# ESP-01_Tamer-u.net
KiCad netlist of a schematic drawn in EAGLE
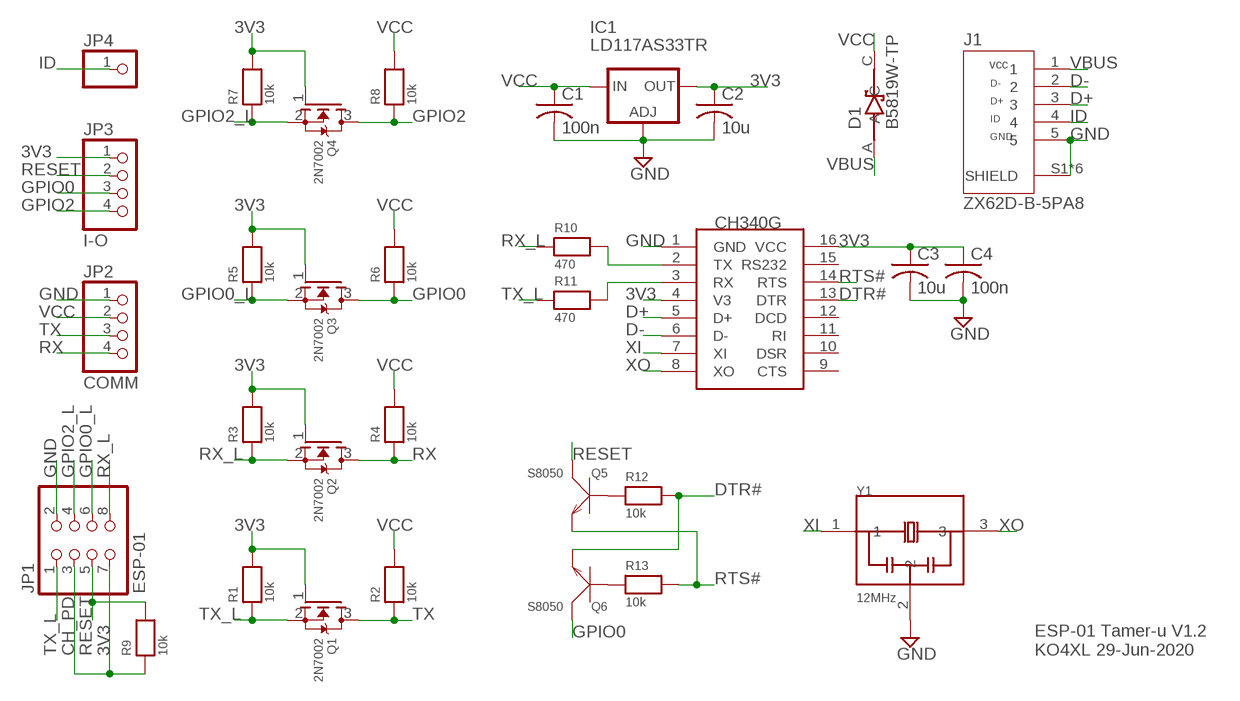
[diagram p0: schematic, sheet 1]

(export (version "E")
  (design (tool "Eeschema 10.0.6"))
  (components
    (comp (ref "C1")
      (value "100n")
      (footprint "eagle-import:C0805K")
      (libsource (lib "eagle-import") (part "C-USC0805K"))
    )
    (comp (ref "C2")
      (value "10u")
      (footprint "eagle-import:C0805K")
      (libsource (lib "eagle-import") (part "C-USC0805K"))
    )
    (comp (ref "C3")
      (value "10u")
      (footprint "eagle-import:C0805K")
      (libsource (lib "eagle-import") (part "C-USC0805K"))
    )
    (comp (ref "C4")
      (value "100n")
      (footprint "eagle-import:C0805K")
      (libsource (lib "eagle-import") (part "C-USC0805K"))
    )
    (comp (ref "D1")
      (value "B5819W-TP")
      (footprint "eagle-import:SOD3716X135N")
      (fields (field (name "MF") "Micro Commercial"))
      (libsource (lib "eagle-import") (part "B5819W-TP"))
    )
    (comp (ref "IC1")
      (value "LD117AS33TR")
      (footprint "eagle-import:SOT223")
      (libsource (lib "eagle-import") (part "LD117A?S33TR"))
    )
    (comp (ref "IC2")
      (value "CH340G")
      (footprint "eagle-import:SOIC16")
      (libsource (lib "eagle-import") (part "CH340G"))
    )
    (comp (ref "J1")
      (value "ZX62D-B-5PA8")
      (footprint "eagle-import:HIROSE_ZX62D-B-5PA8")
      (fields (field (name "MF") "Hirose"))
      (libsource (lib "eagle-import") (part "ZX62D-B-5PA8"))
    )
    (comp (ref "JP1")
      (value "ESP-01")
      (footprint "eagle-import:2X04")
      (libsource (lib "eagle-import") (part "PINHD-2X4"))
    )
    (comp (ref "JP2")
      (value "COMM")
      (footprint "eagle-import:1X04_ROUND")
      (libsource (lib "eagle-import") (part "HEADER-1X4ROUND"))
    )
    (comp (ref "JP3")
      (value "I-O")
      (footprint "eagle-import:1X04_ROUND")
      (libsource (lib "eagle-import") (part "HEADER-1X4ROUND"))
    )
    (comp (ref "JP4")
      (value "HEADER-1X1ROUND")
      (footprint "eagle-import:1X01_ROUND")
      (libsource (lib "eagle-import") (part "HEADER-1X1ROUND"))
    )
    (comp (ref "Q1")
      (value "2N7002")
      (footprint "eagle-import:SOT23-WIDE")
      (libsource (lib "eagle-import") (part "MOSFET-NWIDE"))
    )
    (comp (ref "Q2")
      (value "2N7002")
      (footprint "eagle-import:SOT23-WIDE")
      (libsource (lib "eagle-import") (part "MOSFET-NWIDE"))
    )
    (comp (ref "Q3")
      (value "2N7002")
      (footprint "eagle-import:SOT23-WIDE")
      (libsource (lib "eagle-import") (part "MOSFET-NWIDE"))
    )
    (comp (ref "Q4")
      (value "2N7002")
      (footprint "eagle-import:SOT23-WIDE")
      (libsource (lib "eagle-import") (part "MOSFET-NWIDE"))
    )
    (comp (ref "Q5")
      (value "S8050")
      (footprint "eagle-import:SOT-23")
      (fields (field (name "MF") "JCET"))
      (libsource (lib "eagle-import") (part "SMD-TRANSISTORS-NPN-25V-500MW-S8050(SOT-23)"))
    )
    (comp (ref "Q6")
      (value "S8050")
      (footprint "eagle-import:SOT-23")
      (fields (field (name "MF") "JCET"))
      (libsource (lib "eagle-import") (part "SMD-TRANSISTORS-NPN-25V-500MW-S8050(SOT-23)"))
    )
    (comp (ref "R1")
      (value "10k")
      (footprint "eagle-import:0805_NOTHERMALS")
      (libsource (lib "eagle-import") (part "RESISTOR0805_NOTHERMALS"))
    )
    (comp (ref "R2")
      (value "10k")
      (footprint "eagle-import:0805_NOTHERMALS")
      (libsource (lib "eagle-import") (part "RESISTOR0805_NOTHERMALS"))
    )
    (comp (ref "R3")
      (value "10k")
      (footprint "eagle-import:0805_NOTHERMALS")
      (libsource (lib "eagle-import") (part "RESISTOR0805_NOTHERMALS"))
    )
    (comp (ref "R4")
      (value "10k")
      (footprint "eagle-import:0805_NOTHERMALS")
      (libsource (lib "eagle-import") (part "RESISTOR0805_NOTHERMALS"))
    )
    (comp (ref "R5")
      (value "10k")
      (footprint "eagle-import:0805_NOTHERMALS")
      (libsource (lib "eagle-import") (part "RESISTOR0805_NOTHERMALS"))
    )
    (comp (ref "R6")
      (value "10k")
      (footprint "eagle-import:0805_NOTHERMALS")
      (libsource (lib "eagle-import") (part "RESISTOR0805_NOTHERMALS"))
    )
    (comp (ref "R7")
      (value "10k")
      (footprint "eagle-import:0805_NOTHERMALS")
      (libsource (lib "eagle-import") (part "RESISTOR0805_NOTHERMALS"))
    )
    (comp (ref "R8")
      (value "10k")
      (footprint "eagle-import:0805_NOTHERMALS")
      (libsource (lib "eagle-import") (part "RESISTOR0805_NOTHERMALS"))
    )
    (comp (ref "R9")
      (value "10k")
      (footprint "eagle-import:0805_NOTHERMALS")
      (libsource (lib "eagle-import") (part "RESISTOR0805_NOTHERMALS"))
    )
    (comp (ref "R10")
      (value "470")
      (footprint "eagle-import:0805_NOTHERMALS")
      (libsource (lib "eagle-import") (part "RESISTOR0805_NOTHERMALS"))
    )
    (comp (ref "R11")
      (value "470")
      (footprint "eagle-import:0805_NOTHERMALS")
      (libsource (lib "eagle-import") (part "RESISTOR0805_NOTHERMALS"))
    )
    (comp (ref "R12")
      (value "10k")
      (footprint "eagle-import:0805_NOTHERMALS")
      (libsource (lib "eagle-import") (part "RESISTOR0805_NOTHERMALS"))
    )
    (comp (ref "R13")
      (value "10k")
      (footprint "eagle-import:0805_NOTHERMALS")
      (libsource (lib "eagle-import") (part "RESISTOR0805_NOTHERMALS"))
    )
    (comp (ref "Y1")
      (value "12MHz")
      (footprint "eagle-import:OSC_CSTCE8M00G55-R0")
      (fields (field (name "MF") "Murata") (field (name "MP") "CSTCE8M00G55-R0"))
      (libsource (lib "eagle-import") (part "CSTCE8M00G55-R0"))
    )
  )
  (nets
    (net (code "1") (name "/3V3") (class "Default")
      (node (ref "C2") (pin "1") (pinfunction "1_1") (pintype "passive"))
      (node (ref "C3") (pin "1") (pinfunction "1_1") (pintype "passive"))
      (node (ref "C4") (pin "1") (pinfunction "1_1") (pintype "passive"))
      (node (ref "IC1") (pin "4") (pinfunction "OUT_4") (pintype "passive"))
      (node (ref "IC2") (pin "16") (pinfunction "VCC_16") (pintype "bidirectional"))
      (node (ref "IC2") (pin "4") (pinfunction "V3_4") (pintype "bidirectional"))
      (node (ref "JP1") (pin "3") (pinfunction "3_3") (pintype "passive"))
      (node (ref "JP1") (pin "7") (pinfunction "7_7") (pintype "passive"))
      (node (ref "JP3") (pin "1") (pinfunction "1_1") (pintype "passive"))
      (node (ref "Q1") (pin "1") (pinfunction "G_1") (pintype "bidirectional"))
      (node (ref "Q2") (pin "1") (pinfunction "G_1") (pintype "bidirectional"))
      (node (ref "Q3") (pin "1") (pinfunction "G_1") (pintype "bidirectional"))
      (node (ref "Q4") (pin "1") (pinfunction "G_1") (pintype "bidirectional"))
      (node (ref "R1") (pin "2") (pinfunction "2_2") (pintype "passive"))
      (node (ref "R3") (pin "2") (pinfunction "2_2") (pintype "passive"))
      (node (ref "R5") (pin "2") (pinfunction "2_2") (pintype "passive"))
      (node (ref "R7") (pin "2") (pinfunction "2_2") (pintype "passive"))
      (node (ref "R9") (pin "1") (pinfunction "1_1") (pintype "passive"))
    )
    (net (code "2") (name "/D+") (class "Default")
      (node (ref "IC2") (pin "5") (pinfunction "D+_5") (pintype "bidirectional"))
      (node (ref "J1") (pin "3") (pinfunction "3_3") (pintype "passive"))
    )
    (net (code "3") (name "/D-") (class "Default")
      (node (ref "IC2") (pin "6") (pinfunction "D-_6") (pintype "bidirectional"))
      (node (ref "J1") (pin "2") (pinfunction "2_2") (pintype "passive"))
    )
    (net (code "4") (name "/DTR#") (class "Default")
      (node (ref "IC2") (pin "13") (pinfunction "DTR_13") (pintype "bidirectional"))
      (node (ref "Q6") (pin "2") (pinfunction "E_2") (pintype "passive"))
      (node (ref "R12") (pin "2") (pinfunction "2_2") (pintype "passive"))
    )
    (net (code "5") (name "/GPIO0") (class "Default")
      (node (ref "JP3") (pin "3") (pinfunction "3_3") (pintype "passive"))
      (node (ref "Q3") (pin "3") (pinfunction "D_3") (pintype "bidirectional"))
      (node (ref "Q6") (pin "3") (pinfunction "C_3") (pintype "passive"))
      (node (ref "R6") (pin "1") (pinfunction "1_1") (pintype "passive"))
    )
    (net (code "6") (name "/GPIO0_L") (class "Default")
      (node (ref "JP1") (pin "6") (pinfunction "6_6") (pintype "passive"))
      (node (ref "Q3") (pin "2") (pinfunction "S_2") (pintype "bidirectional"))
      (node (ref "R5") (pin "1") (pinfunction "1_1") (pintype "passive"))
    )
    (net (code "7") (name "/GPIO2") (class "Default")
      (node (ref "JP3") (pin "4") (pinfunction "4_4") (pintype "passive"))
      (node (ref "Q4") (pin "3") (pinfunction "D_3") (pintype "bidirectional"))
      (node (ref "R8") (pin "1") (pinfunction "1_1") (pintype "passive"))
    )
    (net (code "8") (name "/GPIO2_L") (class "Default")
      (node (ref "JP1") (pin "4") (pinfunction "4_4") (pintype "passive"))
      (node (ref "Q4") (pin "2") (pinfunction "S_2") (pintype "bidirectional"))
      (node (ref "R7") (pin "1") (pinfunction "1_1") (pintype "passive"))
    )
    (net (code "9") (name "/ID") (class "Default")
      (node (ref "J1") (pin "4") (pinfunction "4_4") (pintype "passive"))
      (node (ref "JP4") (pin "1") (pinfunction "1_1") (pintype "passive"))
    )
    (net (code "10") (name "/RESET") (class "Default")
      (node (ref "JP1") (pin "5") (pinfunction "5_5") (pintype "passive"))
      (node (ref "JP3") (pin "2") (pinfunction "2_2") (pintype "passive"))
      (node (ref "Q5") (pin "3") (pinfunction "C_3") (pintype "passive"))
      (node (ref "R9") (pin "2") (pinfunction "2_2") (pintype "passive"))
    )
    (net (code "11") (name "/RTS#") (class "Default")
      (node (ref "IC2") (pin "14") (pinfunction "RTS_14") (pintype "bidirectional"))
      (node (ref "Q5") (pin "2") (pinfunction "E_2") (pintype "passive"))
      (node (ref "R13") (pin "2") (pinfunction "2_2") (pintype "passive"))
    )
    (net (code "12") (name "/RX") (class "Default")
      (node (ref "JP2") (pin "4") (pinfunction "4_4") (pintype "passive"))
      (node (ref "Q2") (pin "3") (pinfunction "D_3") (pintype "bidirectional"))
      (node (ref "R4") (pin "1") (pinfunction "1_1") (pintype "passive"))
    )
    (net (code "13") (name "/RX_L") (class "Default")
      (node (ref "JP1") (pin "8") (pinfunction "8_8") (pintype "passive"))
      (node (ref "Q2") (pin "2") (pinfunction "S_2") (pintype "bidirectional"))
      (node (ref "R10") (pin "1") (pinfunction "1_1") (pintype "passive"))
      (node (ref "R3") (pin "1") (pinfunction "1_1") (pintype "passive"))
    )
    (net (code "14") (name "/TX") (class "Default")
      (node (ref "JP2") (pin "3") (pinfunction "3_3") (pintype "passive"))
      (node (ref "Q1") (pin "3") (pinfunction "D_3") (pintype "bidirectional"))
      (node (ref "R2") (pin "1") (pinfunction "1_1") (pintype "passive"))
    )
    (net (code "15") (name "/TX_L") (class "Default")
      (node (ref "JP1") (pin "1") (pinfunction "1_1") (pintype "passive"))
      (node (ref "Q1") (pin "2") (pinfunction "S_2") (pintype "bidirectional"))
      (node (ref "R1") (pin "1") (pinfunction "1_1") (pintype "passive"))
      (node (ref "R11") (pin "1") (pinfunction "1_1") (pintype "passive"))
    )
    (net (code "16") (name "/VBUS") (class "Default")
      (node (ref "D1") (pin "A") (pinfunction "A_A") (pintype "passive"))
      (node (ref "J1") (pin "1") (pinfunction "1_1") (pintype "passive"))
    )
    (net (code "17") (name "/VCC") (class "Default")
      (node (ref "C1") (pin "1") (pinfunction "1_1") (pintype "passive"))
      (node (ref "D1") (pin "C") (pinfunction "C_C") (pintype "passive"))
      (node (ref "IC1") (pin "3") (pinfunction "IN_3") (pintype "input"))
      (node (ref "JP2") (pin "2") (pinfunction "2_2") (pintype "passive"))
      (node (ref "R2") (pin "2") (pinfunction "2_2") (pintype "passive"))
      (node (ref "R4") (pin "2") (pinfunction "2_2") (pintype "passive"))
      (node (ref "R6") (pin "2") (pinfunction "2_2") (pintype "passive"))
      (node (ref "R8") (pin "2") (pinfunction "2_2") (pintype "passive"))
    )
    (net (code "18") (name "/XI") (class "Default")
      (node (ref "IC2") (pin "7") (pinfunction "XI_7") (pintype "bidirectional"))
      (node (ref "Y1") (pin "1") (pinfunction "1_1") (pintype "passive"))
    )
    (net (code "19") (name "/XO") (class "Default")
      (node (ref "IC2") (pin "8") (pinfunction "XO_8") (pintype "bidirectional"))
      (node (ref "Y1") (pin "3") (pinfunction "3_3") (pintype "passive"))
    )
    (net (code "20") (name "GND") (class "Default")
      (node (ref "C1") (pin "2") (pinfunction "2_2") (pintype "passive"))
      (node (ref "C2") (pin "2") (pinfunction "2_2") (pintype "passive"))
      (node (ref "C3") (pin "2") (pinfunction "2_2") (pintype "passive"))
      (node (ref "C4") (pin "2") (pinfunction "2_2") (pintype "passive"))
      (node (ref "IC1") (pin "1") (pinfunction "ADJ_1") (pintype "input"))
      (node (ref "IC2") (pin "1") (pinfunction "GND_1") (pintype "bidirectional"))
      (node (ref "J1") (pin "5") (pinfunction "5_5") (pintype "passive"))
      (node (ref "J1") (pin "S1") (pinfunction "SHIELD_S1") (pintype "power_in"))
      (node (ref "J1") (pin "S2") (pinfunction "SHIELD_S2") (pintype "power_in"))
      (node (ref "J1") (pin "S3") (pinfunction "SHIELD_S3") (pintype "power_in"))
      (node (ref "J1") (pin "S4") (pinfunction "SHIELD_S4") (pintype "power_in"))
      (node (ref "J1") (pin "S5") (pinfunction "SHIELD_S5") (pintype "power_in"))
      (node (ref "J1") (pin "S6") (pinfunction "SHIELD_S6") (pintype "power_in"))
      (node (ref "JP1") (pin "2") (pinfunction "2_2") (pintype "passive"))
      (node (ref "JP2") (pin "1") (pinfunction "1_1") (pintype "passive"))
      (node (ref "Y1") (pin "2") (pinfunction "2_2") (pintype "power_in"))
    )
    (net (code "21") (name "Net-(IC2-RX)") (class "Default")
      (node (ref "IC2") (pin "3") (pinfunction "RX_3") (pintype "bidirectional"))
      (node (ref "R11") (pin "2") (pinfunction "2_2") (pintype "passive"))
    )
    (net (code "22") (name "Net-(IC2-TX)") (class "Default")
      (node (ref "IC2") (pin "2") (pinfunction "TX_2") (pintype "bidirectional"))
      (node (ref "R10") (pin "2") (pinfunction "2_2") (pintype "passive"))
    )
    (net (code "23") (name "Net-(Q5-B)") (class "Default")
      (node (ref "Q5") (pin "1") (pinfunction "B_1") (pintype "passive"))
      (node (ref "R12") (pin "1") (pinfunction "1_1") (pintype "passive"))
    )
    (net (code "24") (name "Net-(Q6-B)") (class "Default")
      (node (ref "Q6") (pin "1") (pinfunction "B_1") (pintype "passive"))
      (node (ref "R13") (pin "1") (pinfunction "1_1") (pintype "passive"))
    )
    (net (code "25") (name "unconnected-(IC2-CTS-Pad9)") (class "Default")
      (node (ref "IC2") (pin "9") (pinfunction "CTS_9") (pintype "bidirectional"))
    )
    (net (code "26") (name "unconnected-(IC2-DCD-Pad12)") (class "Default")
      (node (ref "IC2") (pin "12") (pinfunction "DCD_12") (pintype "bidirectional"))
    )
    (net (code "27") (name "unconnected-(IC2-DSR-Pad10)") (class "Default")
      (node (ref "IC2") (pin "10") (pinfunction "DSR_10") (pintype "bidirectional"))
    )
    (net (code "28") (name "unconnected-(IC2-RI-Pad11)") (class "Default")
      (node (ref "IC2") (pin "11") (pinfunction "RI_11") (pintype "bidirectional"))
    )
    (net (code "29") (name "unconnected-(IC2-RS232-Pad15)") (class "Default")
      (node (ref "IC2") (pin "15") (pinfunction "RS232_15") (pintype "bidirectional"))
    )
  )
)
